# UROV_ESC_Mounts.net
KiCad netlist of a schematic drawn in Altium Designer
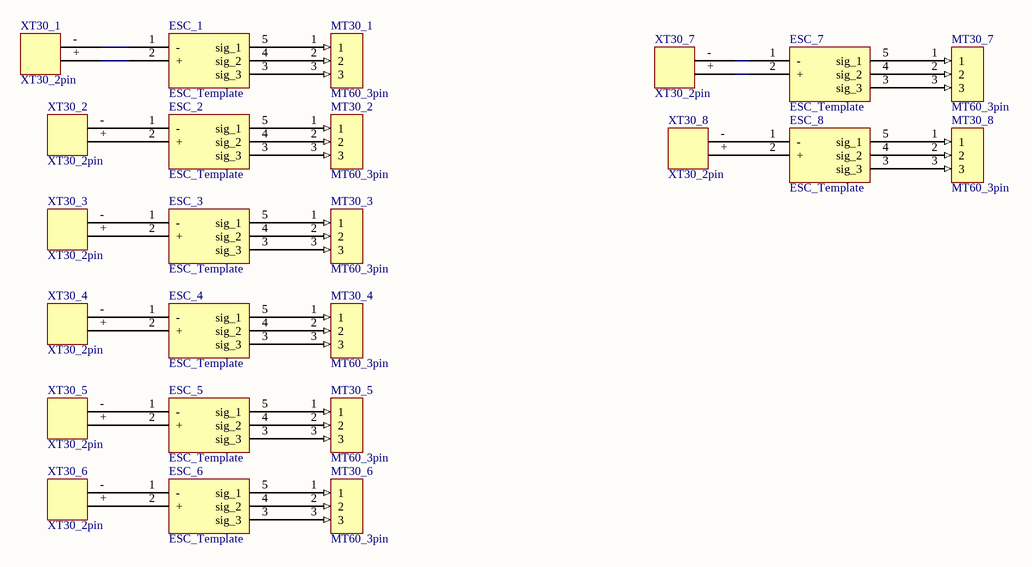
[diagram p0: UROV_ESC_Mounts.SchDoc]

(export (version "E")
  (design (tool "Eeschema 10.0.6"))
  (components
    (comp (ref "ESC_1")
      (value "ESC_Template")
      (footprint "ESC_mounts")
      (libsource (lib "UROV_Aux_Lib") (part "ESC_Template"))
    )
    (comp (ref "ESC_2")
      (value "ESC_Template")
      (footprint "ESC_mounts")
      (libsource (lib "UROV_Aux_Lib") (part "ESC_Template"))
    )
    (comp (ref "ESC_3")
      (value "ESC_Template")
      (footprint "ESC_mounts")
      (libsource (lib "UROV_Aux_Lib") (part "ESC_Template"))
    )
    (comp (ref "ESC_4")
      (value "ESC_Template")
      (footprint "ESC_mounts")
      (libsource (lib "UROV_Aux_Lib") (part "ESC_Template"))
    )
    (comp (ref "ESC_5")
      (value "ESC_Template")
      (footprint "ESC_mounts")
      (libsource (lib "UROV_Aux_Lib") (part "ESC_Template"))
    )
    (comp (ref "ESC_6")
      (value "ESC_Template")
      (footprint "ESC_mounts")
      (libsource (lib "UROV_Aux_Lib") (part "ESC_Template"))
    )
    (comp (ref "ESC_7")
      (value "ESC_Template")
      (footprint "ESC_mounts")
      (libsource (lib "UROV_Aux_Lib") (part "ESC_Template"))
    )
    (comp (ref "ESC_8")
      (value "ESC_Template")
      (footprint "ESC_mounts")
      (libsource (lib "UROV_Aux_Lib") (part "ESC_Template"))
    )
    (comp (ref "MT30_1")
      (value "MT60_3pin")
      (footprint "MT60_3pin")
      (libsource (lib "UROV_Aux_Lib") (part "MT60_3pin"))
    )
    (comp (ref "MT30_2")
      (value "MT60_3pin")
      (footprint "MT60_3pin")
      (libsource (lib "UROV_Aux_Lib") (part "MT60_3pin"))
    )
    (comp (ref "MT30_3")
      (value "MT60_3pin")
      (footprint "MT60_3pin")
      (libsource (lib "UROV_Aux_Lib") (part "MT60_3pin"))
    )
    (comp (ref "MT30_4")
      (value "MT60_3pin")
      (footprint "MT60_3pin")
      (libsource (lib "UROV_Aux_Lib") (part "MT60_3pin"))
    )
    (comp (ref "MT30_5")
      (value "MT60_3pin")
      (footprint "MT60_3pin")
      (libsource (lib "UROV_Aux_Lib") (part "MT60_3pin"))
    )
    (comp (ref "MT30_6")
      (value "MT60_3pin")
      (footprint "MT60_3pin")
      (libsource (lib "UROV_Aux_Lib") (part "MT60_3pin"))
    )
    (comp (ref "MT30_7")
      (value "MT60_3pin")
      (footprint "MT60_3pin")
      (libsource (lib "UROV_Aux_Lib") (part "MT60_3pin"))
    )
    (comp (ref "MT30_8")
      (value "MT60_3pin")
      (footprint "MT60_3pin")
      (libsource (lib "UROV_Aux_Lib") (part "MT60_3pin"))
    )
    (comp (ref "XT30_1")
      (value "XT30_2pin")
      (footprint "XT30_2pin")
      (libsource (lib "UROV_Aux_Lib") (part "XT30_2pin"))
    )
    (comp (ref "XT30_2")
      (value "XT30_2pin")
      (footprint "XT30_2pin")
      (libsource (lib "UROV_Aux_Lib") (part "XT30_2pin"))
    )
    (comp (ref "XT30_3")
      (value "XT30_2pin")
      (footprint "XT30_2pin")
      (libsource (lib "UROV_Aux_Lib") (part "XT30_2pin"))
    )
    (comp (ref "XT30_4")
      (value "XT30_2pin")
      (footprint "XT30_2pin")
      (libsource (lib "UROV_Aux_Lib") (part "XT30_2pin"))
    )
    (comp (ref "XT30_5")
      (value "XT30_2pin")
      (footprint "XT30_2pin")
      (libsource (lib "UROV_Aux_Lib") (part "XT30_2pin"))
    )
    (comp (ref "XT30_6")
      (value "XT30_2pin")
      (footprint "XT30_2pin")
      (libsource (lib "UROV_Aux_Lib") (part "XT30_2pin"))
    )
    (comp (ref "XT30_7")
      (value "XT30_2pin")
      (footprint "XT30_2pin")
      (libsource (lib "UROV_Aux_Lib") (part "XT30_2pin"))
    )
    (comp (ref "XT30_8")
      (value "XT30_2pin")
      (footprint "XT30_2pin")
      (libsource (lib "UROV_Aux_Lib") (part "XT30_2pin"))
    )
  )
  (nets
    (net (code "1") (name "Net-(ESC_1-+)") (class "Default")
      (node (ref "ESC_1") (pin "2") (pinfunction "+_2") (pintype "passive"))
      (node (ref "XT30_1") (pin "+") (pintype "passive"))
    )
    (net (code "2") (name "Net-(ESC_1--)") (class "Default")
      (node (ref "ESC_1") (pin "1") (pinfunction "-_1") (pintype "passive"))
      (node (ref "XT30_1") (pin "-") (pintype "passive"))
    )
    (net (code "3") (name "Net-(ESC_1-sig_1)") (class "Default")
      (node (ref "ESC_1") (pin "5") (pinfunction "sig_1_5") (pintype "passive"))
      (node (ref "MT30_1") (pin "1") (pinfunction "1_1") (pintype "input"))
    )
    (net (code "4") (name "Net-(ESC_1-sig_2)") (class "Default")
      (node (ref "ESC_1") (pin "4") (pinfunction "sig_2_4") (pintype "passive"))
      (node (ref "MT30_1") (pin "2") (pinfunction "2_2") (pintype "input"))
    )
    (net (code "5") (name "Net-(ESC_1-sig_3)") (class "Default")
      (node (ref "ESC_1") (pin "3") (pinfunction "sig_3_3") (pintype "passive"))
      (node (ref "MT30_1") (pin "3") (pinfunction "3_3") (pintype "input"))
    )
    (net (code "6") (name "Net-(ESC_2-+)") (class "Default")
      (node (ref "ESC_2") (pin "2") (pinfunction "+_2") (pintype "passive"))
      (node (ref "XT30_2") (pin "+") (pintype "passive"))
    )
    (net (code "7") (name "Net-(ESC_2--)") (class "Default")
      (node (ref "ESC_2") (pin "1") (pinfunction "-_1") (pintype "passive"))
      (node (ref "XT30_2") (pin "-") (pintype "passive"))
    )
    (net (code "8") (name "Net-(ESC_2-sig_1)") (class "Default")
      (node (ref "ESC_2") (pin "5") (pinfunction "sig_1_5") (pintype "passive"))
      (node (ref "MT30_2") (pin "1") (pinfunction "1_1") (pintype "input"))
    )
    (net (code "9") (name "Net-(ESC_2-sig_2)") (class "Default")
      (node (ref "ESC_2") (pin "4") (pinfunction "sig_2_4") (pintype "passive"))
      (node (ref "MT30_2") (pin "2") (pinfunction "2_2") (pintype "input"))
    )
    (net (code "10") (name "Net-(ESC_2-sig_3)") (class "Default")
      (node (ref "ESC_2") (pin "3") (pinfunction "sig_3_3") (pintype "passive"))
      (node (ref "MT30_2") (pin "3") (pinfunction "3_3") (pintype "input"))
    )
    (net (code "11") (name "Net-(ESC_3-+)") (class "Default")
      (node (ref "ESC_3") (pin "2") (pinfunction "+_2") (pintype "passive"))
      (node (ref "XT30_3") (pin "+") (pintype "passive"))
    )
    (net (code "12") (name "Net-(ESC_3--)") (class "Default")
      (node (ref "ESC_3") (pin "1") (pinfunction "-_1") (pintype "passive"))
      (node (ref "XT30_3") (pin "-") (pintype "passive"))
    )
    (net (code "13") (name "Net-(ESC_3-sig_1)") (class "Default")
      (node (ref "ESC_3") (pin "5") (pinfunction "sig_1_5") (pintype "passive"))
      (node (ref "MT30_3") (pin "1") (pinfunction "1_1") (pintype "input"))
    )
    (net (code "14") (name "Net-(ESC_3-sig_2)") (class "Default")
      (node (ref "ESC_3") (pin "4") (pinfunction "sig_2_4") (pintype "passive"))
      (node (ref "MT30_3") (pin "2") (pinfunction "2_2") (pintype "input"))
    )
    (net (code "15") (name "Net-(ESC_3-sig_3)") (class "Default")
      (node (ref "ESC_3") (pin "3") (pinfunction "sig_3_3") (pintype "passive"))
      (node (ref "MT30_3") (pin "3") (pinfunction "3_3") (pintype "input"))
    )
    (net (code "16") (name "Net-(ESC_4-+)") (class "Default")
      (node (ref "ESC_4") (pin "2") (pinfunction "+_2") (pintype "passive"))
      (node (ref "XT30_4") (pin "+") (pintype "passive"))
    )
    (net (code "17") (name "Net-(ESC_4--)") (class "Default")
      (node (ref "ESC_4") (pin "1") (pinfunction "-_1") (pintype "passive"))
      (node (ref "XT30_4") (pin "-") (pintype "passive"))
    )
    (net (code "18") (name "Net-(ESC_4-sig_1)") (class "Default")
      (node (ref "ESC_4") (pin "5") (pinfunction "sig_1_5") (pintype "passive"))
      (node (ref "MT30_4") (pin "1") (pinfunction "1_1") (pintype "input"))
    )
    (net (code "19") (name "Net-(ESC_4-sig_2)") (class "Default")
      (node (ref "ESC_4") (pin "4") (pinfunction "sig_2_4") (pintype "passive"))
      (node (ref "MT30_4") (pin "2") (pinfunction "2_2") (pintype "input"))
    )
    (net (code "20") (name "Net-(ESC_4-sig_3)") (class "Default")
      (node (ref "ESC_4") (pin "3") (pinfunction "sig_3_3") (pintype "passive"))
      (node (ref "MT30_4") (pin "3") (pinfunction "3_3") (pintype "input"))
    )
    (net (code "21") (name "Net-(ESC_5-+)") (class "Default")
      (node (ref "ESC_5") (pin "2") (pinfunction "+_2") (pintype "passive"))
      (node (ref "XT30_5") (pin "+") (pintype "passive"))
    )
    (net (code "22") (name "Net-(ESC_5--)") (class "Default")
      (node (ref "ESC_5") (pin "1") (pinfunction "-_1") (pintype "passive"))
      (node (ref "XT30_5") (pin "-") (pintype "passive"))
    )
    (net (code "23") (name "Net-(ESC_5-sig_1)") (class "Default")
      (node (ref "ESC_5") (pin "5") (pinfunction "sig_1_5") (pintype "passive"))
      (node (ref "MT30_5") (pin "1") (pinfunction "1_1") (pintype "input"))
    )
    (net (code "24") (name "Net-(ESC_5-sig_2)") (class "Default")
      (node (ref "ESC_5") (pin "4") (pinfunction "sig_2_4") (pintype "passive"))
      (node (ref "MT30_5") (pin "2") (pinfunction "2_2") (pintype "input"))
    )
    (net (code "25") (name "Net-(ESC_5-sig_3)") (class "Default")
      (node (ref "ESC_5") (pin "3") (pinfunction "sig_3_3") (pintype "passive"))
      (node (ref "MT30_5") (pin "3") (pinfunction "3_3") (pintype "input"))
    )
    (net (code "26") (name "Net-(ESC_6-+)") (class "Default")
      (node (ref "ESC_6") (pin "2") (pinfunction "+_2") (pintype "passive"))
      (node (ref "XT30_6") (pin "+") (pintype "passive"))
    )
    (net (code "27") (name "Net-(ESC_6--)") (class "Default")
      (node (ref "ESC_6") (pin "1") (pinfunction "-_1") (pintype "passive"))
      (node (ref "XT30_6") (pin "-") (pintype "passive"))
    )
    (net (code "28") (name "Net-(ESC_6-sig_1)") (class "Default")
      (node (ref "ESC_6") (pin "5") (pinfunction "sig_1_5") (pintype "passive"))
      (node (ref "MT30_6") (pin "1") (pinfunction "1_1") (pintype "input"))
    )
    (net (code "29") (name "Net-(ESC_6-sig_2)") (class "Default")
      (node (ref "ESC_6") (pin "4") (pinfunction "sig_2_4") (pintype "passive"))
      (node (ref "MT30_6") (pin "2") (pinfunction "2_2") (pintype "input"))
    )
    (net (code "30") (name "Net-(ESC_6-sig_3)") (class "Default")
      (node (ref "ESC_6") (pin "3") (pinfunction "sig_3_3") (pintype "passive"))
      (node (ref "MT30_6") (pin "3") (pinfunction "3_3") (pintype "input"))
    )
    (net (code "31") (name "Net-(ESC_7-+)") (class "Default")
      (node (ref "ESC_7") (pin "2") (pinfunction "+_2") (pintype "passive"))
      (node (ref "XT30_7") (pin "+") (pintype "passive"))
    )
    (net (code "32") (name "Net-(ESC_7--)") (class "Default")
      (node (ref "ESC_7") (pin "1") (pinfunction "-_1") (pintype "passive"))
      (node (ref "XT30_7") (pin "-") (pintype "passive"))
    )
    (net (code "33") (name "Net-(ESC_7-sig_1)") (class "Default")
      (node (ref "ESC_7") (pin "5") (pinfunction "sig_1_5") (pintype "passive"))
      (node (ref "MT30_7") (pin "1") (pinfunction "1_1") (pintype "input"))
    )
    (net (code "34") (name "Net-(ESC_7-sig_2)") (class "Default")
      (node (ref "ESC_7") (pin "4") (pinfunction "sig_2_4") (pintype "passive"))
      (node (ref "MT30_7") (pin "2") (pinfunction "2_2") (pintype "input"))
    )
    (net (code "35") (name "Net-(ESC_7-sig_3)") (class "Default")
      (node (ref "ESC_7") (pin "3") (pinfunction "sig_3_3") (pintype "passive"))
      (node (ref "MT30_7") (pin "3") (pinfunction "3_3") (pintype "input"))
    )
    (net (code "36") (name "Net-(ESC_8-+)") (class "Default")
      (node (ref "ESC_8") (pin "2") (pinfunction "+_2") (pintype "passive"))
      (node (ref "XT30_8") (pin "+") (pintype "passive"))
    )
    (net (code "37") (name "Net-(ESC_8--)") (class "Default")
      (node (ref "ESC_8") (pin "1") (pinfunction "-_1") (pintype "passive"))
      (node (ref "XT30_8") (pin "-") (pintype "passive"))
    )
    (net (code "38") (name "Net-(ESC_8-sig_1)") (class "Default")
      (node (ref "ESC_8") (pin "5") (pinfunction "sig_1_5") (pintype "passive"))
      (node (ref "MT30_8") (pin "1") (pinfunction "1_1") (pintype "input"))
    )
    (net (code "39") (name "Net-(ESC_8-sig_2)") (class "Default")
      (node (ref "ESC_8") (pin "4") (pinfunction "sig_2_4") (pintype "passive"))
      (node (ref "MT30_8") (pin "2") (pinfunction "2_2") (pintype "input"))
    )
    (net (code "40") (name "Net-(ESC_8-sig_3)") (class "Default")
      (node (ref "ESC_8") (pin "3") (pinfunction "sig_3_3") (pintype "passive"))
      (node (ref "MT30_8") (pin "3") (pinfunction "3_3") (pintype "input"))
    )
  )
)
